# Main.net
KiCad netlist of a schematic drawn in Altium Designer
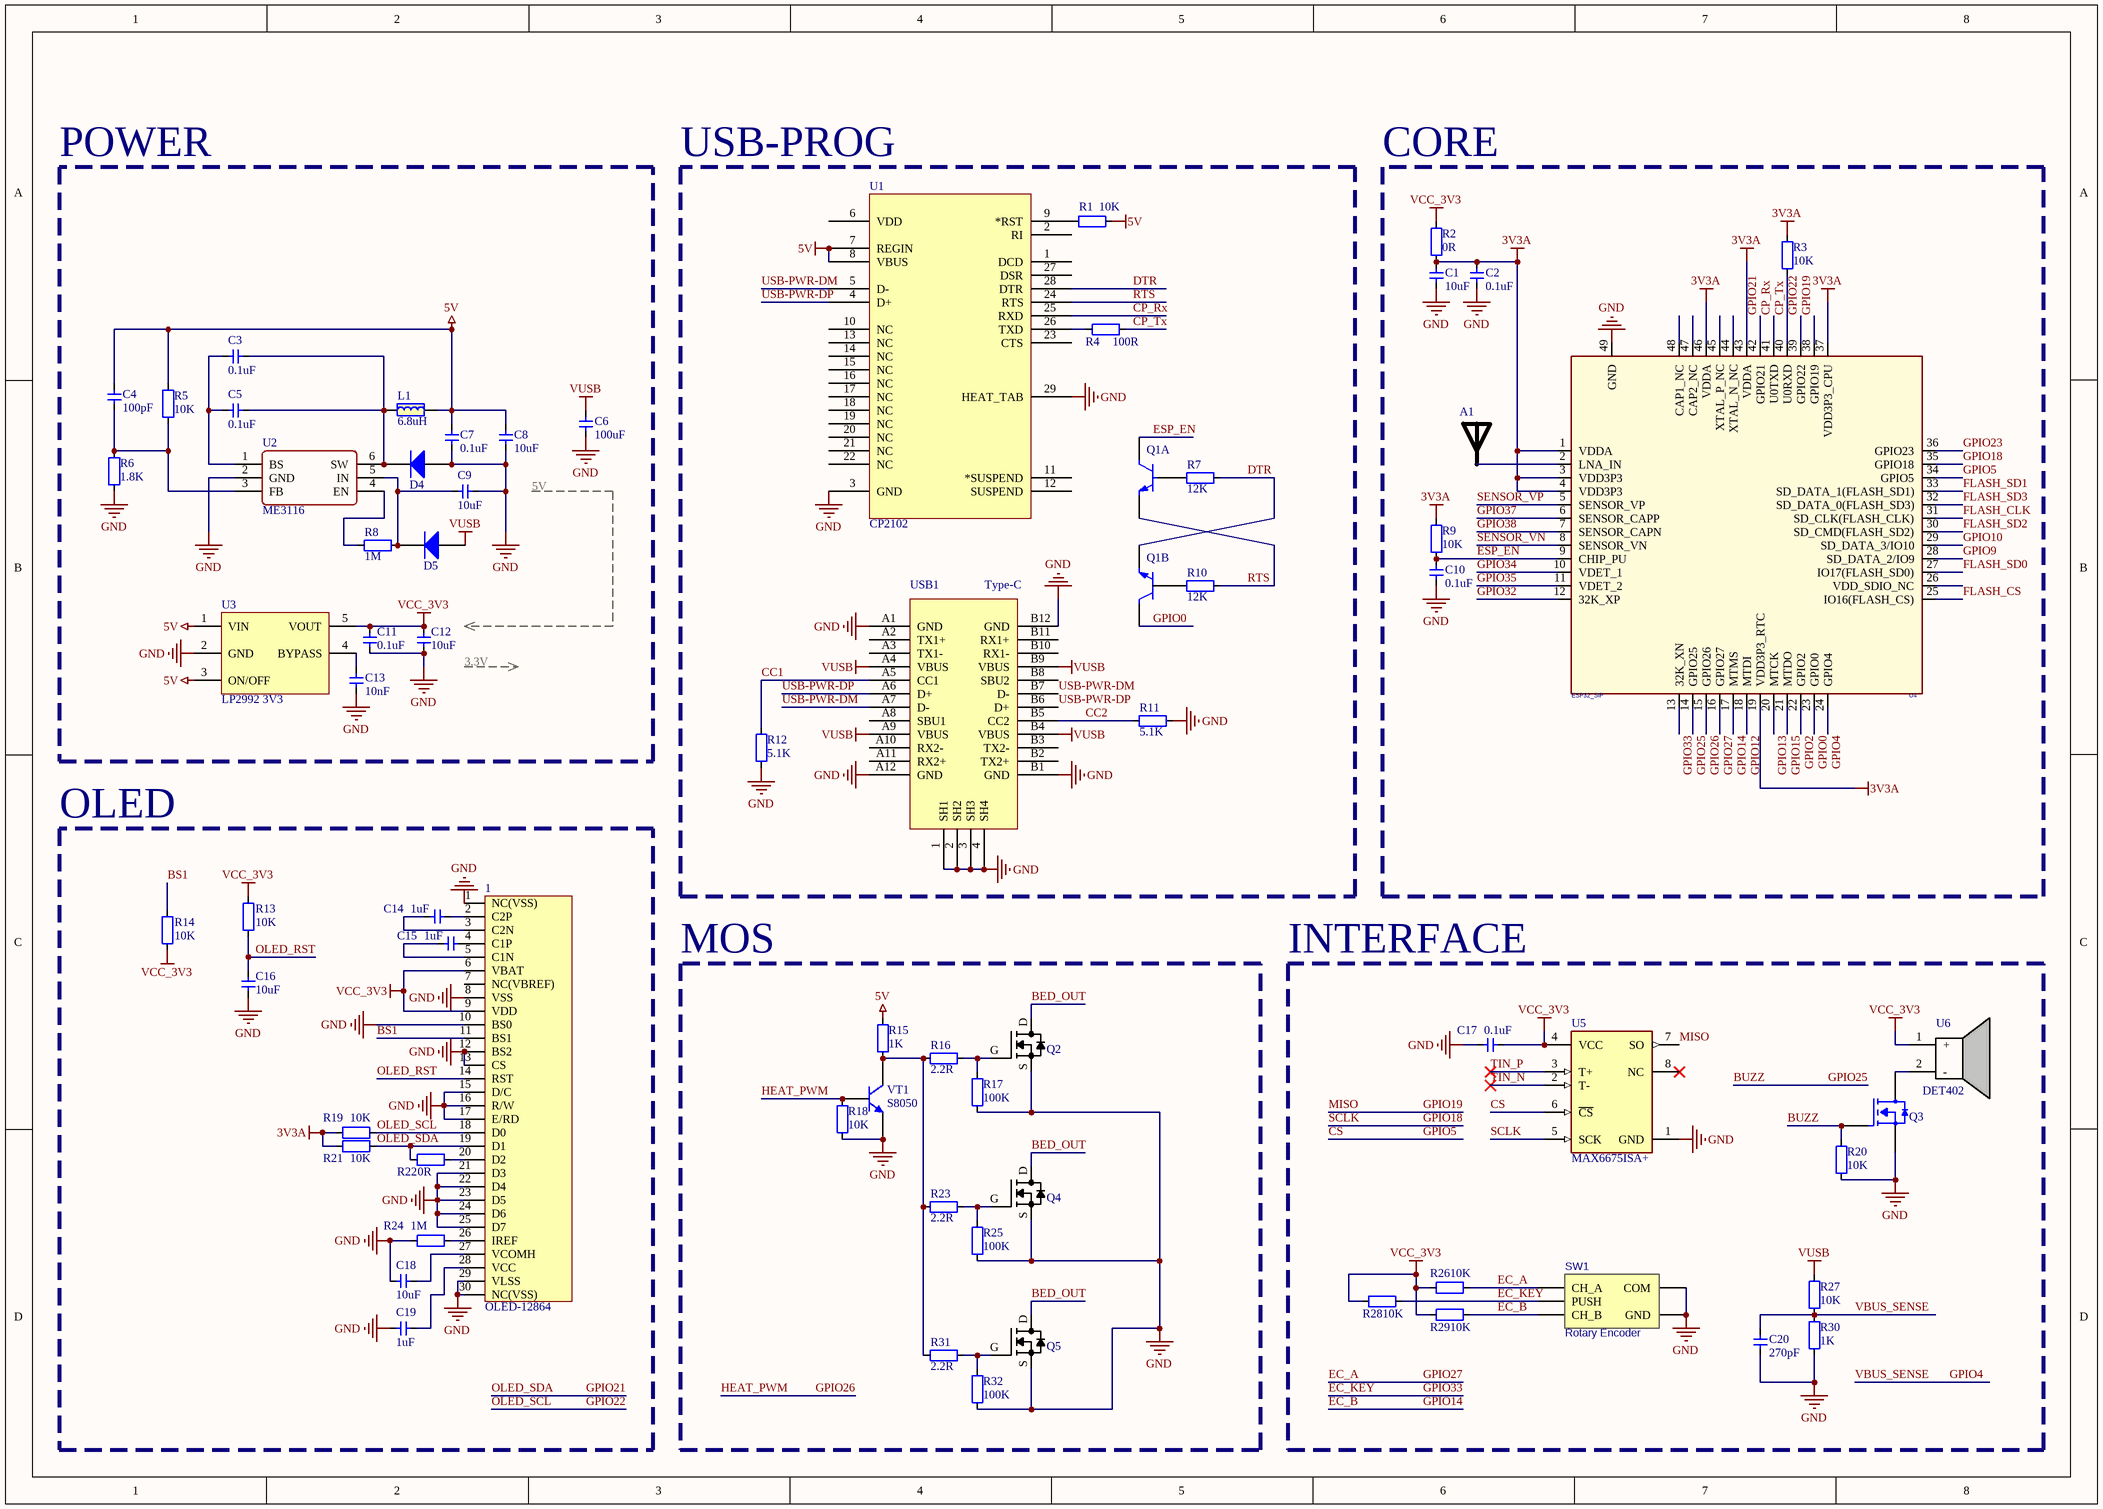
[diagram p0: Main.SchDoc]

(export (version "E")
  (design (tool "Eeschema 10.0.6"))
  (components
    (comp (ref "1")
      (value "OLED-12864")
      (footprint "OLED-12864-1.3-TOP")
      (description "显示屏")
      (libsource (lib "MyPcbLib") (part "OLED-12864"))
    )
    (comp (ref "A1")
      (value "RAINSUN")
      (footprint "ANT-Rainsun-AN5120")
      (libsource (lib "MyPcbLib") (part "ANT-Rainsun-AP5120"))
    )
    (comp (ref "C1")
      (value "10uF")
      (footprint "CAP_0402")
      (description "Capacitor")
      (libsource (lib "MyPcbLib") (part "电容-0402"))
    )
    (comp (ref "C2")
      (value "0.1uF")
      (footprint "CAP_0402")
      (description "Capacitor")
      (libsource (lib "MyPcbLib") (part "电容-0402"))
    )
    (comp (ref "C3")
      (value "0.1uF")
      (footprint "CAP_0402")
      (description "Capacitor")
      (libsource (lib "MyPcbLib") (part "电容-0402"))
    )
    (comp (ref "C4")
      (value "100pF")
      (footprint "CAP_0402")
      (description "Capacitor")
      (libsource (lib "MyPcbLib") (part "电容-0402"))
    )
    (comp (ref "C5")
      (value "0.1uF")
      (footprint "CAP_0402")
      (description "Capacitor")
      (libsource (lib "MyPcbLib") (part "电容-0402"))
    )
    (comp (ref "C6")
      (value "100uF")
      (footprint "1206-CAP")
      (description "Capacitor")
      (libsource (lib "MyPcbLib") (part "电容-1206"))
    )
    (comp (ref "C7")
      (value "0.1uF")
      (footprint "CAP_0402")
      (description "Capacitor")
      (libsource (lib "MyPcbLib") (part "电容-0402"))
    )
    (comp (ref "C8")
      (value "10uF")
      (footprint "CAP_0402")
      (description "Capacitor")
      (libsource (lib "MyPcbLib") (part "电容-0402"))
    )
    (comp (ref "C9")
      (value "10uF")
      (footprint "CAP_0402")
      (description "Capacitor")
      (libsource (lib "MyPcbLib") (part "电容-0402"))
    )
    (comp (ref "C10")
      (value "0.1uF")
      (footprint "CAP_0402")
      (description "Capacitor")
      (libsource (lib "MyPcbLib") (part "电容-0402"))
    )
    (comp (ref "C11")
      (value "0.1uF")
      (footprint "CAP_0402")
      (description "Capacitor")
      (libsource (lib "MyPcbLib") (part "电容-0402"))
    )
    (comp (ref "C12")
      (value "10uF")
      (footprint "CAP_0402")
      (description "Capacitor")
      (libsource (lib "MyPcbLib") (part "电容-0402"))
    )
    (comp (ref "C13")
      (value "10nF")
      (footprint "CAP_0402")
      (description "Capacitor")
      (libsource (lib "MyPcbLib") (part "电容-0402"))
    )
    (comp (ref "C14")
      (value "1uF")
      (footprint "CAP_0402")
      (description "Capacitor")
      (libsource (lib "MyPcbLib") (part "电容-0402"))
    )
    (comp (ref "C15")
      (value "1uF")
      (footprint "CAP_0402")
      (description "Capacitor")
      (libsource (lib "MyPcbLib") (part "电容-0402"))
    )
    (comp (ref "C16")
      (value "10uF")
      (footprint "CAP_0402")
      (description "Capacitor")
      (libsource (lib "MyPcbLib") (part "电容-0402"))
    )
    (comp (ref "C17")
      (value "0.1uF")
      (footprint "CAP_0402")
      (description "Capacitor")
      (libsource (lib "MyPcbLib") (part "电容-0402"))
    )
    (comp (ref "C18")
      (value "10uF")
      (footprint "CAP_0402")
      (description "Capacitor")
      (libsource (lib "MyPcbLib") (part "电容-0402"))
    )
    (comp (ref "C19")
      (value "1uF")
      (footprint "CAP_0402")
      (description "Capacitor")
      (libsource (lib "MyPcbLib") (part "电容-0402"))
    )
    (comp (ref "C20")
      (value "270pF")
      (footprint "CAP_0402")
      (description "Capacitor")
      (libsource (lib "MyPcbLib") (part "电容-0402"))
    )
    (comp (ref "D4")
      (value "二极管-5819W")
      (footprint "SOD-323")
      (description "40V")
      (libsource (lib "MyPcbLib") (part "二极管-5819W"))
    )
    (comp (ref "D5")
      (value "二极管-5819W")
      (footprint "SOD-323")
      (description "40V")
      (libsource (lib "MyPcbLib") (part "二极管-5819W"))
    )
    (comp (ref "L1") (value "6.8uH") (footprint "IND-201612") (libsource (lib "MyPcbLib") (part "电感-201612")))
    (comp (ref "Q1")
      (value "BC847BVC-7")
      (footprint "SOT563-6")
      (libsource (lib "MyPcbLib") (part "BC847BVC-7"))
    )
    (comp (ref "Q2")
      (value "NTMFS5C628NLT")
      (footprint "SO8FL")
      (description "MOSFET N-CH 60V SO8FL")
      (fields
        (field (name "MANUFACTURER") "ON Semiconductor")
        (field (name "MANUFACTURER PART NUMBER") "NTMFS5C628NLT1G")
      )
      (libsource (lib "MyPcbLib") (part "NTMFS5C628NLT"))
    )
    (comp (ref "Q3")
      (value "AO3400A")
      (footprint "SOT23-3")
      (description "N-MOS")
      (libsource (lib "MyPcbLib") (part "AO3400A"))
    )
    (comp (ref "Q4")
      (value "NTMFS5C628NLT")
      (footprint "SO8FL")
      (description "MOSFET N-CH 60V SO8FL")
      (fields
        (field (name "MANUFACTURER") "ON Semiconductor")
        (field (name "MANUFACTURER PART NUMBER") "NTMFS5C628NLT1G")
      )
      (libsource (lib "MyPcbLib") (part "NTMFS5C628NLT"))
    )
    (comp (ref "Q5")
      (value "NTMFS5C628NLT")
      (footprint "SO8FL")
      (description "MOSFET N-CH 60V SO8FL")
      (fields
        (field (name "MANUFACTURER") "ON Semiconductor")
        (field (name "MANUFACTURER PART NUMBER") "NTMFS5C628NLT1G")
      )
      (libsource (lib "MyPcbLib") (part "NTMFS5C628NLT"))
    )
    (comp (ref "R1")
      (value "10K")
      (footprint "RES_0402")
      (description "Resistor")
      (libsource (lib "MyPcbLib") (part "电阻-0402"))
    )
    (comp (ref "R2")
      (value "0R")
      (footprint "RES_0402")
      (description "Resistor")
      (libsource (lib "") (part "电阻-0402_1"))
    )
    (comp (ref "R3")
      (value "10K")
      (footprint "RES_0402")
      (description "Resistor")
      (libsource (lib "") (part "电阻-0402_2"))
    )
    (comp (ref "R4")
      (value "100R")
      (footprint "RES_0402")
      (description "Resistor")
      (libsource (lib "MyPcbLib") (part "电阻-0402"))
    )
    (comp (ref "R5")
      (value "10K")
      (footprint "RES_0402")
      (description "Resistor")
      (libsource (lib "") (part "电阻-0402_2"))
    )
    (comp (ref "R6")
      (value "1.8K")
      (footprint "RES_0402")
      (description "Resistor")
      (libsource (lib "") (part "电阻-0402_2"))
    )
    (comp (ref "R7")
      (value "12K")
      (footprint "RES_0402")
      (description "Resistor")
      (libsource (lib "MyPcbLib") (part "电阻-0402"))
    )
    (comp (ref "R8")
      (value "1M")
      (footprint "RES_0402")
      (description "Resistor")
      (libsource (lib "MyPcbLib") (part "电阻-0402"))
    )
    (comp (ref "R9")
      (value "10K")
      (footprint "RES_0402")
      (description "Resistor")
      (libsource (lib "") (part "电阻-0402_1"))
    )
    (comp (ref "R10")
      (value "12K")
      (footprint "RES_0402")
      (description "Resistor")
      (libsource (lib "MyPcbLib") (part "电阻-0402"))
    )
    (comp (ref "R11")
      (value "5.1K")
      (footprint "RES_0402")
      (description "Resistor")
      (libsource (lib "MyPcbLib") (part "电阻-0402"))
    )
    (comp (ref "R12")
      (value "5.1K")
      (footprint "RES_0402")
      (description "Resistor")
      (libsource (lib "") (part "电阻-0402_1"))
    )
    (comp (ref "R13")
      (value "10K")
      (footprint "RES_0402")
      (description "Resistor")
      (libsource (lib "") (part "电阻-0402_2"))
    )
    (comp (ref "R14")
      (value "10K")
      (footprint "RES_0402")
      (description "Resistor")
      (libsource (lib "") (part "电阻-0402_2"))
    )
    (comp (ref "R15")
      (value "1K")
      (footprint "RES_0402")
      (description "Resistor")
      (libsource (lib "") (part "电阻-0402_2"))
    )
    (comp (ref "R16")
      (value "2.2R")
      (footprint "RES_0402")
      (description "Resistor")
      (libsource (lib "MyPcbLib") (part "电阻-0402"))
    )
    (comp (ref "R17")
      (value "100K")
      (footprint "RES_0402")
      (description "Resistor")
      (libsource (lib "") (part "电阻-0402_1"))
    )
    (comp (ref "R18")
      (value "10K")
      (footprint "RES_0402")
      (description "Resistor")
      (libsource (lib "") (part "电阻-0402_1"))
    )
    (comp (ref "R19")
      (value "10K")
      (footprint "RES_0402")
      (description "Resistor")
      (libsource (lib "") (part "电阻-0402_3"))
    )
    (comp (ref "R20")
      (value "10K")
      (footprint "RES_0402")
      (description "Resistor")
      (libsource (lib "") (part "电阻-0402_2"))
    )
    (comp (ref "R21")
      (value "10K")
      (footprint "RES_0402")
      (description "Resistor")
      (libsource (lib "") (part "电阻-0402_3"))
    )
    (comp (ref "R22")
      (value "0R")
      (footprint "RES_0402")
      (description "Resistor")
      (libsource (lib "MyPcbLib") (part "电阻-0402"))
    )
    (comp (ref "R23")
      (value "2.2R")
      (footprint "RES_0402")
      (description "Resistor")
      (libsource (lib "MyPcbLib") (part "电阻-0402"))
    )
    (comp (ref "R24")
      (value "1M")
      (footprint "RES_0402")
      (description "Resistor")
      (libsource (lib "") (part "电阻-0402_3"))
    )
    (comp (ref "R25")
      (value "100K")
      (footprint "RES_0402")
      (description "Resistor")
      (libsource (lib "") (part "电阻-0402_1"))
    )
    (comp (ref "R26")
      (value "10K")
      (footprint "RES_0402")
      (description "Resistor")
      (libsource (lib "MyPcbLib") (part "电阻-0402"))
    )
    (comp (ref "R27")
      (value "10K")
      (footprint "RES_0402")
      (description "Resistor")
      (libsource (lib "") (part "电阻-0402_1"))
    )
    (comp (ref "R28")
      (value "10K")
      (footprint "RES_0402")
      (description "Resistor")
      (libsource (lib "MyPcbLib") (part "电阻-0402"))
    )
    (comp (ref "R29")
      (value "10K")
      (footprint "RES_0402")
      (description "Resistor")
      (libsource (lib "MyPcbLib") (part "电阻-0402"))
    )
    (comp (ref "R30")
      (value "1K")
      (footprint "RES_0402")
      (description "Resistor")
      (libsource (lib "") (part "电阻-0402_1"))
    )
    (comp (ref "R31")
      (value "2.2R")
      (footprint "RES_0402")
      (description "Resistor")
      (libsource (lib "MyPcbLib") (part "电阻-0402"))
    )
    (comp (ref "R32")
      (value "100K")
      (footprint "RES_0402")
      (description "Resistor")
      (libsource (lib "") (part "电阻-0402_1"))
    )
    (comp (ref "SW1")
      (value "Rotary Encoder")
      (footprint "SIQ-02FVS3")
      (fields
        (field (name "BOM_SUPPLIER PART") "C1322543")
        (field (name "BOM_MANUFACTURER PART") "EC11E1534443")
        (field (name "CONTRIBUTOR") "LCSC")
      )
      (libsource (lib "MyPcbLib") (part "Rotary Encoder"))
    )
    (comp (ref "U1")
      (value "CP2102")
      (footprint "QFN-28")
      (description "USB转TTL")
      (libsource (lib "mLib") (part "CP2102"))
    )
    (comp (ref "U2")
      (value "ME3116")
      (footprint "SOT23-6")
      (description "DC-DC")
      (libsource (lib "MyPcbLib") (part "ME3116"))
    )
    (comp (ref "U3")
      (value "LP2992 3V3")
      (footprint "SOT23-5")
      (description "LDO")
      (libsource (lib "mLib") (part "LP2992"))
    )
    (comp (ref "U4")
      (value "ESP32_SIP")
      (footprint "QFN-48_7X7")
      (libsource (lib "mLib") (part "ESP32-PICO"))
    )
    (comp (ref "U5")
      (value "MAX6675ISA")
      (footprint "SO-8")
      (description "IC THERMOCOUP TO DGTL 8-SOIC")
      (fields
        (field (name "MANUFACTURER") "Maxim Electronics")
        (field (name "OCTOPART PART NUMBER") "33bcfab92ad8ec7b")
        (field (name "PART NUMBER") "MAX6675ISA+")
      )
      (libsource (lib "MyPcbLib") (part "MAX6675ISA"))
    )
    (comp (ref "U6") (value "DET402") (footprint "DET402") (libsource (lib "MyPcbLib") (part "DET402")))
    (comp (ref "USB1")
      (value "Type-C")
      (footprint "Type-C-TOP")
      (libsource (lib "MyPcbLib") (part "USB-Type-C-TOP"))
    )
    (comp (ref "VT1")
      (value "S8050")
      (footprint "SMT_TRIODE_NPN")
      (description "Surface mount NPN transistor, package SOT-23")
      (libsource (lib "MyPcbLib") (part "SMT_TRIODE_NPN"))
    )
  )
  (nets
    (net (code "1") (name "/BED_OUT") (class "Default")
      (node (ref "Q2") (pin "D") (pinfunction "D_D") (pintype "passive"))
      (node (ref "Q4") (pin "D") (pinfunction "D_D") (pintype "passive"))
      (node (ref "Q5") (pin "D") (pinfunction "D_D") (pintype "passive"))
    )
    (net (code "2") (name "/BS1") (class "Default")
      (node (ref "1") (pin "11") (pinfunction "BS1_11") (pintype "passive"))
      (node (ref "R14") (pin "2") (pinfunction "2_2") (pintype "passive"))
    )
    (net (code "3") (name "/BUZZ") (class "Default")
      (node (ref "Q3") (pin "1") (pinfunction "G_1") (pintype "passive"))
      (node (ref "R20") (pin "2") (pinfunction "2_2") (pintype "passive"))
      (node (ref "U4") (pin "14") (pinfunction "GPIO25_14") (pintype "passive"))
    )
    (net (code "4") (name "/CC1") (class "Default")
      (node (ref "R12") (pin "1") (pinfunction "1_1") (pintype "passive"))
      (node (ref "USB1") (pin "A5") (pinfunction "CC1_A5") (pintype "passive"))
    )
    (net (code "5") (name "/CC2") (class "Default")
      (node (ref "R11") (pin "2") (pinfunction "2_2") (pintype "passive"))
      (node (ref "USB1") (pin "B5") (pinfunction "CC2_B5") (pintype "passive"))
    )
    (net (code "6") (name "/CP_Rx") (class "Default")
      (node (ref "U1") (pin "25") (pinfunction "RXD_25") (pintype "passive"))
      (node (ref "U4") (pin "41") (pinfunction "U0TXD_41") (pintype "power_in"))
    )
    (net (code "7") (name "/CP_Tx") (class "Default")
      (node (ref "R3") (pin "1") (pinfunction "1_1") (pintype "passive"))
      (node (ref "R4") (pin "1") (pinfunction "1_1") (pintype "passive"))
      (node (ref "U4") (pin "40") (pinfunction "U0RXD_40") (pintype "power_in"))
    )
    (net (code "8") (name "/CS") (class "Default")
      (node (ref "U4") (pin "34") (pinfunction "GPIO5_34") (pintype "passive"))
      (node (ref "U5") (pin "6") (pinfunction "~{CS}_6") (pintype "input"))
    )
    (net (code "9") (name "/DTR") (class "Default")
      (node (ref "Q1") (pin "4") (pinfunction "E2_4") (pintype "passive"))
      (node (ref "R7") (pin "1") (pinfunction "1_1") (pintype "passive"))
      (node (ref "U1") (pin "28") (pinfunction "DTR_28") (pintype "passive"))
    )
    (net (code "10") (name "/EC_A") (class "Default")
      (node (ref "R26") (pin "1") (pinfunction "1_1") (pintype "passive"))
      (node (ref "SW1") (pin "1") (pinfunction "CH_A_1") (pintype "passive"))
      (node (ref "U4") (pin "16") (pinfunction "GPIO27_16") (pintype "passive"))
    )
    (net (code "11") (name "/EC_B") (class "Default")
      (node (ref "R29") (pin "1") (pinfunction "1_1") (pintype "passive"))
      (node (ref "SW1") (pin "4") (pinfunction "CH_B_4") (pintype "passive"))
      (node (ref "U4") (pin "17") (pinfunction "MTMS_17") (pintype "passive"))
    )
    (net (code "12") (name "/EC_KEY") (class "Default")
      (node (ref "R28") (pin "1") (pinfunction "1_1") (pintype "passive"))
      (node (ref "SW1") (pin "2") (pinfunction "PUSH_2") (pintype "passive"))
      (node (ref "U4") (pin "13") (pinfunction "32K_XN_13") (pintype "passive"))
    )
    (net (code "13") (name "/ESP_EN") (class "Default")
      (node (ref "C10") (pin "1") (pinfunction "1_1") (pintype "passive"))
      (node (ref "Q1") (pin "6") (pinfunction "C1_6") (pintype "passive"))
      (node (ref "R9") (pin "2") (pinfunction "2_2") (pintype "passive"))
      (node (ref "U4") (pin "9") (pinfunction "CHIP_PU_9") (pintype "passive"))
    )
    (net (code "14") (name "/FLASH_CLK") (class "Default")
      (node (ref "U4") (pin "31") (pinfunction "SD_CLK(FLASH_CLK)_31") (pintype "passive"))
    )
    (net (code "15") (name "/FLASH_CS") (class "Default")
      (node (ref "U4") (pin "25") (pinfunction "IO16(FLASH_CS)_25") (pintype "passive"))
    )
    (net (code "16") (name "/FLASH_SD0") (class "Default")
      (node (ref "U4") (pin "27") (pinfunction "IO17(FLASH_SD0)_27") (pintype "passive"))
    )
    (net (code "17") (name "/FLASH_SD1") (class "Default")
      (node (ref "U4") (pin "33") (pinfunction "SD_DATA_1(FLASH_SD1)_33") (pintype "passive"))
    )
    (net (code "18") (name "/FLASH_SD2") (class "Default")
      (node (ref "U4") (pin "30") (pinfunction "SD_CMD(FLASH_SD2)_30") (pintype "passive"))
    )
    (net (code "19") (name "/FLASH_SD3") (class "Default")
      (node (ref "U4") (pin "32") (pinfunction "SD_DATA_0(FLASH_SD3)_32") (pintype "passive"))
    )
    (net (code "20") (name "/GPIO0") (class "Default")
      (node (ref "Q1") (pin "3") (pinfunction "C2_3") (pintype "passive"))
      (node (ref "U4") (pin "23") (pinfunction "GPIO0_23") (pintype "passive"))
    )
    (net (code "21") (name "/GPIO2") (class "Default")
      (node (ref "U4") (pin "22") (pinfunction "GPIO2_22") (pintype "passive"))
    )
    (net (code "22") (name "/GPIO4") (class "Default")
      (node (ref "C20") (pin "2") (pinfunction "2_2") (pintype "passive"))
      (node (ref "R27") (pin "2") (pinfunction "2_2") (pintype "passive"))
      (node (ref "R30") (pin "1") (pinfunction "1_1") (pintype "passive"))
      (node (ref "U4") (pin "24") (pinfunction "GPIO4_24") (pintype "passive"))
    )
    (net (code "23") (name "/GPIO9") (class "Default")
      (node (ref "U4") (pin "28") (pinfunction "SD_DATA_2/IO9_28") (pintype "passive"))
    )
    (net (code "24") (name "/GPIO10") (class "Default")
      (node (ref "U4") (pin "29") (pinfunction "SD_DATA_3/IO10_29") (pintype "passive"))
    )
    (net (code "25") (name "/GPIO12") (class "Default")
      (node (ref "U4") (pin "18") (pinfunction "MTDI_18") (pintype "passive"))
    )
    (net (code "26") (name "/GPIO13") (class "Default")
      (node (ref "U4") (pin "20") (pinfunction "MTCK_20") (pintype "passive"))
    )
    (net (code "27") (name "/GPIO15") (class "Default")
      (node (ref "U4") (pin "21") (pinfunction "MTDO_21") (pintype "passive"))
    )
    (net (code "28") (name "/GPIO18") (class "Default")
      (node (ref "U4") (pin "35") (pinfunction "GPIO18_35") (pintype "passive"))
      (node (ref "U5") (pin "5") (pinfunction "SCK_5") (pintype "input"))
    )
    (net (code "29") (name "/GPIO19") (class "Default")
      (node (ref "U4") (pin "38") (pinfunction "GPIO19_38") (pintype "passive"))
      (node (ref "U5") (pin "7") (pinfunction "SO_7") (pintype "output"))
    )
    (net (code "30") (name "/GPIO21") (class "Default")
      (node (ref "1") (pin "19") (pinfunction "D1_19") (pintype "passive"))
      (node (ref "R21") (pin "2") (pinfunction "2_2") (pintype "passive"))
      (node (ref "R22") (pin "2") (pinfunction "2_2") (pintype "passive"))
      (node (ref "U4") (pin "42") (pinfunction "GPIO21_42") (pintype "passive"))
    )
    (net (code "31") (name "/GPIO22") (class "Default")
      (node (ref "1") (pin "18") (pinfunction "D0_18") (pintype "passive"))
      (node (ref "R19") (pin "2") (pinfunction "2_2") (pintype "passive"))
      (node (ref "U4") (pin "39") (pinfunction "GPIO22_39") (pintype "passive"))
    )
    (net (code "32") (name "/GPIO23") (class "Default")
      (node (ref "U4") (pin "36") (pinfunction "GPIO23_36") (pintype "passive"))
    )
    (net (code "33") (name "/GPIO26") (class "Default")
      (node (ref "R18") (pin "1") (pinfunction "1_1") (pintype "passive"))
      (node (ref "U4") (pin "15") (pinfunction "GPIO26_15") (pintype "passive"))
      (node (ref "VT1") (pin "1") (pinfunction "B_1") (pintype "passive"))
    )
    (net (code "34") (name "/GPIO32") (class "Default")
      (node (ref "U4") (pin "12") (pinfunction "32K_XP_12") (pintype "passive"))
    )
    (net (code "35") (name "/GPIO34") (class "Default")
      (node (ref "U4") (pin "10") (pinfunction "VDET_1_10") (pintype "passive"))
    )
    (net (code "36") (name "/GPIO35") (class "Default")
      (node (ref "U4") (pin "11") (pinfunction "VDET_2_11") (pintype "passive"))
    )
    (net (code "37") (name "/GPIO37") (class "Default")
      (node (ref "U4") (pin "6") (pinfunction "SENSOR_CAPP_6") (pintype "passive"))
    )
    (net (code "38") (name "/GPIO38") (class "Default")
      (node (ref "U4") (pin "7") (pinfunction "SENSOR_CAPN_7") (pintype "passive"))
    )
    (net (code "39") (name "/OLED_RST") (class "Default")
      (node (ref "1") (pin "14") (pinfunction "RST_14") (pintype "passive"))
      (node (ref "C16") (pin "2") (pinfunction "2_2") (pintype "passive"))
      (node (ref "R13") (pin "1") (pinfunction "1_1") (pintype "passive"))
    )
    (net (code "40") (name "/RTS") (class "Default")
      (node (ref "Q1") (pin "1") (pinfunction "E1_1") (pintype "passive"))
      (node (ref "R10") (pin "1") (pinfunction "1_1") (pintype "passive"))
      (node (ref "U1") (pin "24") (pinfunction "RTS_24") (pintype "passive"))
    )
    (net (code "41") (name "/SENSOR_VN") (class "Default")
      (node (ref "U4") (pin "8") (pinfunction "SENSOR_VN_8") (pintype "passive"))
    )
    (net (code "42") (name "/SENSOR_VP") (class "Default")
      (node (ref "U4") (pin "5") (pinfunction "SENSOR_VP_5") (pintype "passive"))
    )
    (net (code "43") (name "/TIN_N") (class "Default")
      (node (ref "U5") (pin "2") (pinfunction "T-_2") (pintype "input+no_connect"))
    )
    (net (code "44") (name "/TIN_P") (class "Default")
      (node (ref "U5") (pin "3") (pinfunction "T+_3") (pintype "input+no_connect"))
    )
    (net (code "45") (name "/USB-PWR-DM") (class "Default")
      (node (ref "U1") (pin "5") (pinfunction "D-_5") (pintype "passive"))
      (node (ref "USB1") (pin "A7") (pinfunction "D-_A7") (pintype "passive"))
      (node (ref "USB1") (pin "B7") (pinfunction "D-_B7") (pintype "passive"))
    )
    (net (code "46") (name "/USB-PWR-DP") (class "Default")
      (node (ref "U1") (pin "4") (pinfunction "D+_4") (pintype "passive"))
      (node (ref "USB1") (pin "A6") (pinfunction "D+_A6") (pintype "passive"))
      (node (ref "USB1") (pin "B6") (pinfunction "D+_B6") (pintype "passive"))
    )
    (net (code "47") (name "3V3A") (class "Default")
      (node (ref "C1") (pin "2") (pinfunction "2_2") (pintype "passive"))
      (node (ref "C2") (pin "2") (pinfunction "2_2") (pintype "passive"))
      (node (ref "R19") (pin "1") (pinfunction "1_1") (pintype "passive"))
      (node (ref "R2") (pin "2") (pinfunction "2_2") (pintype "passive"))
      (node (ref "R21") (pin "1") (pinfunction "1_1") (pintype "passive"))
      (node (ref "R3") (pin "2") (pinfunction "2_2") (pintype "passive"))
      (node (ref "R9") (pin "1") (pinfunction "1_1") (pintype "passive"))
      (node (ref "U4") (pin "1") (pinfunction "VDDA_1") (pintype "power_in"))
      (node (ref "U4") (pin "19") (pinfunction "VDD3P3_RTC_19") (pintype "power_in"))
      (node (ref "U4") (pin "3") (pinfunction "VDD3P3_3") (pintype "power_in"))
      (node (ref "U4") (pin "37") (pinfunction "VDD3P3_CPU_37") (pintype "power_in"))
      (node (ref "U4") (pin "4") (pinfunction "VDD3P3_4") (pintype "power_in"))
      (node (ref "U4") (pin "43") (pinfunction "VDDA_43") (pintype "power_in"))
      (node (ref "U4") (pin "46") (pinfunction "VDDA_46") (pintype "power_in"))
    )
    (net (code "48") (name "5V") (class "Default")
      (node (ref "C4") (pin "1") (pinfunction "1_1") (pintype "passive"))
      (node (ref "C7") (pin "2") (pinfunction "2_2") (pintype "passive"))
      (node (ref "C8") (pin "2") (pinfunction "2_2") (pintype "passive"))
      (node (ref "L1") (pin "2") (pinfunction "2_2") (pintype "passive"))
      (node (ref "R1") (pin "1") (pinfunction "1_1") (pintype "passive"))
      (node (ref "R15") (pin "2") (pinfunction "2_2") (pintype "passive"))
      (node (ref "R5") (pin "2") (pinfunction "2_2") (pintype "passive"))
      (node (ref "U1") (pin "7") (pinfunction "REGIN_7") (pintype "passive"))
      (node (ref "U1") (pin "8") (pinfunction "VBUS_8") (pintype "passive"))
      (node (ref "U3") (pin "1") (pinfunction "VIN_1") (pintype "passive"))
      (node (ref "U3") (pin "3") (pinfunction "ON/OFF_3") (pintype "passive"))
    )
    (net (code "49") (name "GND") (class "Default")
      (node (ref "1") (pin "1") (pinfunction "NC(VSS)_1") (pintype "passive"))
      (node (ref "1") (pin "10") (pinfunction "BS0_10") (pintype "passive"))
      (node (ref "1") (pin "12") (pinfunction "BS2_12") (pintype "passive"))
      (node (ref "1") (pin "13") (pinfunction "CS_13") (pintype "passive"))
      (node (ref "1") (pin "15") (pinfunction "D/C_15") (pintype "passive"))
      (node (ref "1") (pin "16") (pinfunction "R/W_16") (pintype "passive"))
      (node (ref "1") (pin "17") (pinfunction "E/RD_17") (pintype "passive"))
      (node (ref "1") (pin "21") (pinfunction "D3_21") (pintype "passive"))
      (node (ref "1") (pin "22") (pinfunction "D4_22") (pintype "passive"))
      (node (ref "1") (pin "23") (pinfunction "D5_23") (pintype "passive"))
      (node (ref "1") (pin "24") (pinfunction "D6_24") (pintype "passive"))
      (node (ref "1") (pin "25") (pinfunction "D7_25") (pintype "passive"))
      (node (ref "1") (pin "29") (pinfunction "VLSS_29") (pintype "passive"))
      (node (ref "1") (pin "30") (pinfunction "NC(VSS)_30") (pintype "passive"))
      (node (ref "1") (pin "8") (pinfunction "VSS_8") (pintype "passive"))
      (node (ref "C1") (pin "1") (pinfunction "1_1") (pintype "passive"))
      (node (ref "C10") (pin "2") (pinfunction "2_2") (pintype "passive"))
      (node (ref "C11") (pin "1") (pinfunction "1_1") (pintype "passive"))
      (node (ref "C12") (pin "1") (pinfunction "1_1") (pintype "passive"))
      (node (ref "C13") (pin "1") (pinfunction "1_1") (pintype "passive"))
      (node (ref "C16") (pin "1") (pinfunction "1_1") (pintype "passive"))
      (node (ref "C17") (pin "2") (pinfunction "2_2") (pintype "passive"))
      (node (ref "C18") (pin "2") (pinfunction "2_2") (pintype "passive"))
      (node (ref "C19") (pin "2") (pinfunction "2_2") (pintype "passive"))
      (node (ref "C2") (pin "1") (pinfunction "1_1") (pintype "passive"))
      (node (ref "C20") (pin "1") (pinfunction "1_1") (pintype "passive"))
      (node (ref "C6") (pin "1") (pinfunction "1_1") (pintype "passive"))
      (node (ref "C7") (pin "1") (pinfunction "1_1") (pintype "passive"))
      (node (ref "C8") (pin "1") (pinfunction "1_1") (pintype "passive"))
      (node (ref "C9") (pin "1") (pinfunction "1_1") (pintype "passive"))
      (node (ref "D4") (pin "1") (pinfunction "A_1") (pintype "passive"))
      (node (ref "Q2") (pin "S") (pinfunction "S_S") (pintype "passive"))
      (node (ref "Q3") (pin "2") (pinfunction "S_2") (pintype "passive"))
      (node (ref "Q4") (pin "S") (pinfunction "S_S") (pintype "passive"))
      (node (ref "Q5") (pin "S") (pinfunction "S_S") (pintype "passive"))
      (node (ref "R11") (pin "1") (pinfunction "1_1") (pintype "passive"))
      (node (ref "R12") (pin "2") (pinfunction "2_2") (pintype "passive"))
      (node (ref "R17") (pin "2") (pinfunction "2_2") (pintype "passive"))
      (node (ref "R18") (pin "2") (pinfunction "2_2") (pintype "passive"))
      (node (ref "R20") (pin "1") (pinfunction "1_1") (pintype "passive"))
      (node (ref "R24") (pin "1") (pinfunction "1_1") (pintype "passive"))
      (node (ref "R25") (pin "2") (pinfunction "2_2") (pintype "passive"))
      (node (ref "R30") (pin "2") (pinfunction "2_2") (pintype "passive"))
      (node (ref "R32") (pin "2") (pinfunction "2_2") (pintype "passive"))
      (node (ref "R6") (pin "1") (pinfunction "1_1") (pintype "passive"))
      (node (ref "SW1") (pin "3") (pinfunction "COM_3") (pintype "passive"))
      (node (ref "SW1") (pin "5") (pinfunction "GND_5") (pintype "passive"))
      (node (ref "U1") (pin "29") (pinfunction "HEAT_TAB_29") (pintype "passive"))
      (node (ref "U1") (pin "3") (pinfunction "GND_3") (pintype "passive"))
      (node (ref "U2") (pin "2") (pinfunction "GND_2") (pintype "passive"))
      (node (ref "U3") (pin "2") (pinfunction "GND_2") (pintype "passive"))
      (node (ref "U4") (pin "49") (pinfunction "GND_49") (pintype "power_in"))
      (node (ref "U5") (pin "1") (pinfunction "GND_1") (pintype "power_in"))
      (node (ref "USB1") (pin "1") (pinfunction "SH1_1") (pintype "passive"))
      (node (ref "USB1") (pin "2") (pinfunction "SH2_2") (pintype "passive"))
      (node (ref "USB1") (pin "3") (pinfunction "SH3_3") (pintype "passive"))
      (node (ref "USB1") (pin "4") (pinfunction "SH4_4") (pintype "passive"))
      (node (ref "USB1") (pin "A1") (pinfunction "GND_A1") (pintype "passive"))
      (node (ref "USB1") (pin "A12") (pinfunction "GND_A12") (pintype "passive"))
      (node (ref "USB1") (pin "B1") (pinfunction "GND_B1") (pintype "passive"))
      (node (ref "USB1") (pin "B12") (pinfunction "GND_B12") (pintype "passive"))
      (node (ref "VT1") (pin "2") (pinfunction "E_2") (pintype "passive"))
    )
    (net (code "50") (name "Net-(1-C1N)") (class "Default")
      (node (ref "1") (pin "5") (pinfunction "C1N_5") (pintype "passive"))
      (node (ref "C15") (pin "2") (pinfunction "2_2") (pintype "passive"))
    )
    (net (code "51") (name "Net-(1-C1P)") (class "Default")
      (node (ref "1") (pin "4") (pinfunction "C1P_4") (pintype "passive"))
      (node (ref "C15") (pin "1") (pinfunction "1_1") (pintype "passive"))
    )
    (net (code "52") (name "Net-(1-C2N)") (class "Default")
      (node (ref "1") (pin "3") (pinfunction "C2N_3") (pintype "passive"))
      (node (ref "C14") (pin "2") (pinfunction "2_2") (pintype "passive"))
    )
    (net (code "53") (name "Net-(1-C2P)") (class "Default")
      (node (ref "1") (pin "2") (pinfunction "C2P_2") (pintype "passive"))
      (node (ref "C14") (pin "1") (pinfunction "1_1") (pintype "passive"))
    )
    (net (code "54") (name "Net-(1-D2)") (class "Default")
      (node (ref "1") (pin "20") (pinfunction "D2_20") (pintype "passive"))
      (node (ref "R22") (pin "1") (pinfunction "1_1") (pintype "passive"))
    )
    (net (code "55") (name "Net-(1-IREF)") (class "Default")
      (node (ref "1") (pin "26") (pinfunction "IREF_26") (pintype "passive"))
      (node (ref "R24") (pin "2") (pinfunction "2_2") (pintype "passive"))
    )
    (net (code "56") (name "Net-(1-VCC)") (class "Default")
      (node (ref "1") (pin "28") (pinfunction "VCC_28") (pintype "passive"))
      (node (ref "C19") (pin "1") (pinfunction "1_1") (pintype "passive"))
    )
    (net (code "57") (name "Net-(1-VCOMH)") (class "Default")
      (node (ref "1") (pin "27") (pinfunction "VCOMH_27") (pintype "passive"))
      (node (ref "C18") (pin "1") (pinfunction "1_1") (pintype "passive"))
    )
    (net (code "58") (name "Net-(D4-K)") (class "Default")
      (node (ref "C3") (pin "1") (pinfunction "1_1") (pintype "passive"))
      (node (ref "C5") (pin "1") (pinfunction "1_1") (pintype "passive"))
      (node (ref "D4") (pin "2") (pinfunction "K_2") (pintype "passive"))
      (node (ref "L1") (pin "1") (pintype "passive"))
      (node (ref "U2") (pin "6") (pinfunction "SW_6") (pintype "passive"))
    )
    (net (code "59") (name "Net-(D5-K)") (class "Default")
      (node (ref "C9") (pin "2") (pinfunction "2_2") (pintype "passive"))
      (node (ref "D5") (pin "2") (pinfunction "K_2") (pintype "passive"))
      (node (ref "R8") (pin "1") (pinfunction "1_1") (pintype "passive"))
      (node (ref "U2") (pin "5") (pinfunction "IN_5") (pintype "passive"))
    )
    (net (code "60") (name "Net-(Q1A-B1)") (class "Default")
      (node (ref "Q1") (pin "2") (pinfunction "B1_2") (pintype "passive"))
      (node (ref "R7") (pin "2") (pinfunction "2_2") (pintype "passive"))
    )
    (net (code "61") (name "Net-(Q1B-B2)") (class "Default")
      (node (ref "Q1") (pin "5") (pinfunction "B2_5") (pintype "passive"))
      (node (ref "R10") (pin "2") (pinfunction "2_2") (pintype "passive"))
    )
    (net (code "62") (name "Net-(Q2-PadG)") (class "Default")
      (node (ref "Q2") (pin "G") (pinfunction "G_G") (pintype "passive"))
      (node (ref "R16") (pin "1") (pinfunction "1_1") (pintype "passive"))
      (node (ref "R17") (pin "1") (pinfunction "1_1") (pintype "passive"))
    )
    (net (code "63") (name "Net-(Q3-D)") (class "Default")
      (node (ref "Q3") (pin "3") (pinfunction "D_3") (pintype "passive"))
      (node (ref "U6") (pin "2") (pinfunction "-_2") (pintype "passive"))
    )
    (net (code "64") (name "Net-(Q4-PadG)") (class "Default")
      (node (ref "Q4") (pin "G") (pinfunction "G_G") (pintype "passive"))
      (node (ref "R23") (pin "1") (pinfunction "1_1") (pintype "passive"))
      (node (ref "R25") (pin "1") (pinfunction "1_1") (pintype "passive"))
    )
    (net (code "65") (name "Net-(Q5-PadG)") (class "Default")
      (node (ref "Q5") (pin "G") (pinfunction "G_G") (pintype "passive"))
      (node (ref "R31") (pin "1") (pinfunction "1_1") (pintype "passive"))
      (node (ref "R32") (pin "1") (pinfunction "1_1") (pintype "passive"))
    )
    (net (code "66") (name "Net-(U1-*RST)") (class "Default")
      (node (ref "R1") (pin "2") (pinfunction "2_2") (pintype "passive"))
      (node (ref "U1") (pin "9") (pinfunction "*RST_9") (pintype "passive"))
    )
    (net (code "67") (name "Net-(U1-TXD)") (class "Default")
      (node (ref "R4") (pin "2") (pinfunction "2_2") (pintype "passive"))
      (node (ref "U1") (pin "26") (pinfunction "TXD_26") (pintype "passive"))
    )
    (net (code "68") (name "Net-(U2-BS)") (class "Default")
      (node (ref "C3") (pin "2") (pinfunction "2_2") (pintype "passive"))
      (node (ref "C5") (pin "2") (pinfunction "2_2") (pintype "passive"))
      (node (ref "U2") (pin "1") (pinfunction "BS_1") (pintype "passive"))
    )
    (net (code "69") (name "Net-(U2-EN)") (class "Default")
      (node (ref "R8") (pin "2") (pinfunction "2_2") (pintype "passive"))
      (node (ref "U2") (pin "4") (pinfunction "EN_4") (pintype "passive"))
    )
    (net (code "70") (name "Net-(U2-FB)") (class "Default")
      (node (ref "C4") (pin "2") (pinfunction "2_2") (pintype "passive"))
      (node (ref "R5") (pin "1") (pinfunction "1_1") (pintype "passive"))
      (node (ref "R6") (pin "2") (pinfunction "2_2") (pintype "passive"))
      (node (ref "U2") (pin "3") (pinfunction "FB_3") (pintype "passive"))
    )
    (net (code "71") (name "Net-(U3-BYPASS)") (class "Default")
      (node (ref "C13") (pin "2") (pinfunction "2_2") (pintype "passive"))
      (node (ref "U3") (pin "4") (pinfunction "BYPASS_4") (pintype "passive"))
    )
    (net (code "72") (name "Net-(U4-LNA_IN)") (class "Default")
      (node (ref "A1") (pin "1") (pinfunction "1_1") (pintype "passive"))
      (node (ref "U4") (pin "2") (pinfunction "LNA_IN_2") (pintype "passive"))
    )
    (net (code "73") (name "Net-(VT1-C)") (class "Default")
      (node (ref "R15") (pin "1") (pinfunction "1_1") (pintype "passive"))
      (node (ref "R16") (pin "2") (pinfunction "2_2") (pintype "passive"))
      (node (ref "R23") (pin "2") (pinfunction "2_2") (pintype "passive"))
      (node (ref "R31") (pin "2") (pinfunction "2_2") (pintype "passive"))
      (node (ref "VT1") (pin "3") (pinfunction "C_3") (pintype "passive"))
    )
    (net (code "74") (name "VCC_3V3") (class "Default")
      (node (ref "1") (pin "6") (pinfunction "VBAT_6") (pintype "passive"))
      (node (ref "1") (pin "9") (pinfunction "VDD_9") (pintype "passive"))
      (node (ref "C11") (pin "2") (pinfunction "2_2") (pintype "passive"))
      (node (ref "C12") (pin "2") (pinfunction "2_2") (pintype "passive"))
      (node (ref "C17") (pin "1") (pinfunction "1_1") (pintype "passive"))
      (node (ref "R13") (pin "2") (pinfunction "2_2") (pintype "passive"))
      (node (ref "R14") (pin "1") (pinfunction "1_1") (pintype "passive"))
      (node (ref "R2") (pin "1") (pinfunction "1_1") (pintype "passive"))
      (node (ref "R26") (pin "2") (pinfunction "2_2") (pintype "passive"))
      (node (ref "R28") (pin "2") (pinfunction "2_2") (pintype "passive"))
      (node (ref "R29") (pin "2") (pinfunction "2_2") (pintype "passive"))
      (node (ref "U3") (pin "5") (pinfunction "VOUT_5") (pintype "passive"))
      (node (ref "U5") (pin "4") (pinfunction "VCC_4") (pintype "power_in"))
      (node (ref "U6") (pin "1") (pinfunction "+_1") (pintype "passive"))
    )
    (net (code "75") (name "VUSB") (class "Default")
      (node (ref "C6") (pin "2") (pinfunction "2_2") (pintype "passive"))
      (node (ref "D5") (pin "1") (pinfunction "A_1") (pintype "passive"))
      (node (ref "R27") (pin "1") (pinfunction "1_1") (pintype "passive"))
      (node (ref "USB1") (pin "A4") (pinfunction "VBUS_A4") (pintype "passive"))
      (node (ref "USB1") (pin "A9") (pinfunction "VBUS_A9") (pintype "passive"))
      (node (ref "USB1") (pin "B4") (pinfunction "VBUS_B4") (pintype "passive"))
      (node (ref "USB1") (pin "B9") (pinfunction "VBUS_B9") (pintype "passive"))
    )
    (net (code "76") (name "unconnected-(1-NC(VBREF)-Pad7)") (class "Default")
      (node (ref "1") (pin "7") (pinfunction "NC(VBREF)_7") (pintype "passive"))
    )
    (net (code "77") (name "unconnected-(U1-*SUSPEND-Pad11)") (class "Default")
      (node (ref "U1") (pin "11") (pinfunction "*SUSPEND_11") (pintype "passive"))
    )
    (net (code "78") (name "unconnected-(U1-CTS-Pad23)") (class "Default")
      (node (ref "U1") (pin "23") (pinfunction "CTS_23") (pintype "passive"))
    )
    (net (code "79") (name "unconnected-(U1-DCD-Pad1)") (class "Default")
      (node (ref "U1") (pin "1") (pinfunction "DCD_1") (pintype "passive"))
    )
    (net (code "80") (name "unconnected-(U1-DSR-Pad27)") (class "Default")
      (node (ref "U1") (pin "27") (pinfunction "DSR_27") (pintype "passive"))
    )
    (net (code "81") (name "unconnected-(U1-NC-Pad10)") (class "Default")
      (node (ref "U1") (pin "10") (pinfunction "NC_10") (pintype "passive"))
    )
    (net (code "82") (name "unconnected-(U1-NC-Pad13)") (class "Default")
      (node (ref "U1") (pin "13") (pinfunction "NC_13") (pintype "passive"))
    )
    (net (code "83") (name "unconnected-(U1-NC-Pad14)") (class "Default")
      (node (ref "U1") (pin "14") (pinfunction "NC_14") (pintype "passive"))
    )
    (net (code "84") (name "unconnected-(U1-NC-Pad15)") (class "Default")
      (node (ref "U1") (pin "15") (pinfunction "NC_15") (pintype "passive"))
    )
    (net (code "85") (name "unconnected-(U1-NC-Pad16)") (class "Default")
      (node (ref "U1") (pin "16") (pinfunction "NC_16") (pintype "passive"))
    )
    (net (code "86") (name "unconnected-(U1-NC-Pad17)") (class "Default")
      (node (ref "U1") (pin "17") (pinfunction "NC_17") (pintype "passive"))
    )
    (net (code "87") (name "unconnected-(U1-NC-Pad18)") (class "Default")
      (node (ref "U1") (pin "18") (pinfunction "NC_18") (pintype "passive"))
    )
    (net (code "88") (name "unconnected-(U1-NC-Pad19)") (class "Default")
      (node (ref "U1") (pin "19") (pinfunction "NC_19") (pintype "passive"))
    )
    (net (code "89") (name "unconnected-(U1-NC-Pad20)") (class "Default")
      (node (ref "U1") (pin "20") (pinfunction "NC_20") (pintype "passive"))
    )
    (net (code "90") (name "unconnected-(U1-NC-Pad21)") (class "Default")
      (node (ref "U1") (pin "21") (pinfunction "NC_21") (pintype "passive"))
    )
    (net (code "91") (name "unconnected-(U1-NC-Pad22)") (class "Default")
      (node (ref "U1") (pin "22") (pinfunction "NC_22") (pintype "passive"))
    )
    (net (code "92") (name "unconnected-(U1-RI-Pad2)") (class "Default")
      (node (ref "U1") (pin "2") (pinfunction "RI_2") (pintype "passive"))
    )
    (net (code "93") (name "unconnected-(U1-SUSPEND-Pad12)") (class "Default")
      (node (ref "U1") (pin "12") (pinfunction "SUSPEND_12") (pintype "passive"))
    )
    (net (code "94") (name "unconnected-(U1-VDD-Pad6)") (class "Default")
      (node (ref "U1") (pin "6") (pinfunction "VDD_6") (pintype "passive"))
    )
    (net (code "95") (name "unconnected-(U4-CAP1_NC-Pad48)") (class "Default")
      (node (ref "U4") (pin "48") (pinfunction "CAP1_NC_48") (pintype "passive"))
    )
    (net (code "96") (name "unconnected-(U4-CAP2_NC-Pad47)") (class "Default")
      (node (ref "U4") (pin "47") (pinfunction "CAP2_NC_47") (pintype "passive"))
    )
    (net (code "97") (name "unconnected-(U4-VDD_SDIO_NC-Pad26)") (class "Default")
      (node (ref "U4") (pin "26") (pinfunction "VDD_SDIO_NC_26") (pintype "passive"))
    )
    (net (code "98") (name "unconnected-(U4-XTAL_N_NC-Pad44)") (class "Default")
      (node (ref "U4") (pin "44") (pinfunction "XTAL_N_NC_44") (pintype "passive"))
    )
    (net (code "99") (name "unconnected-(U4-XTAL_P_NC-Pad45)") (class "Default")
      (node (ref "U4") (pin "45") (pinfunction "XTAL_P_NC_45") (pintype "passive"))
    )
    (net (code "100") (name "unconnected-(U5-NC-Pad8)") (class "Default")
      (node (ref "U5") (pin "8") (pinfunction "NC_8") (pintype "passive+no_connect"))
    )
    (net (code "101") (name "unconnected-(USB1-RX1+-PadB11)") (class "Default")
      (node (ref "USB1") (pin "B11") (pinfunction "RX1+_B11") (pintype "passive"))
    )
    (net (code "102") (name "unconnected-(USB1-RX1--PadB10)") (class "Default")
      (node (ref "USB1") (pin "B10") (pinfunction "RX1-_B10") (pintype "passive"))
    )
    (net (code "103") (name "unconnected-(USB1-RX2+-PadA11)") (class "Default")
      (node (ref "USB1") (pin "A11") (pinfunction "RX2+_A11") (pintype "passive"))
    )
    (net (code "104") (name "unconnected-(USB1-RX2--PadA10)") (class "Default")
      (node (ref "USB1") (pin "A10") (pinfunction "RX2-_A10") (pintype "passive"))
    )
    (net (code "105") (name "unconnected-(USB1-SBU1-PadA8)") (class "Default")
      (node (ref "USB1") (pin "A8") (pinfunction "SBU1_A8") (pintype "passive"))
    )
    (net (code "106") (name "unconnected-(USB1-SBU2-PadB8)") (class "Default")
      (node (ref "USB1") (pin "B8") (pinfunction "SBU2_B8") (pintype "passive"))
    )
    (net (code "107") (name "unconnected-(USB1-TX1+-PadA2)") (class "Default")
      (node (ref "USB1") (pin "A2") (pinfunction "TX1+_A2") (pintype "passive"))
    )
    (net (code "108") (name "unconnected-(USB1-TX1--PadA3)") (class "Default")
      (node (ref "USB1") (pin "A3") (pinfunction "TX1-_A3") (pintype "passive"))
    )
    (net (code "109") (name "unconnected-(USB1-TX2+-PadB2)") (class "Default")
      (node (ref "USB1") (pin "B2") (pinfunction "TX2+_B2") (pintype "passive"))
    )
    (net (code "110") (name "unconnected-(USB1-TX2--PadB3)") (class "Default")
      (node (ref "USB1") (pin "B3") (pinfunction "TX2-_B3") (pintype "passive"))
    )
  )
)
